# MD5133-A01-02.net
KiCad netlist of a schematic drawn in Altium Designer
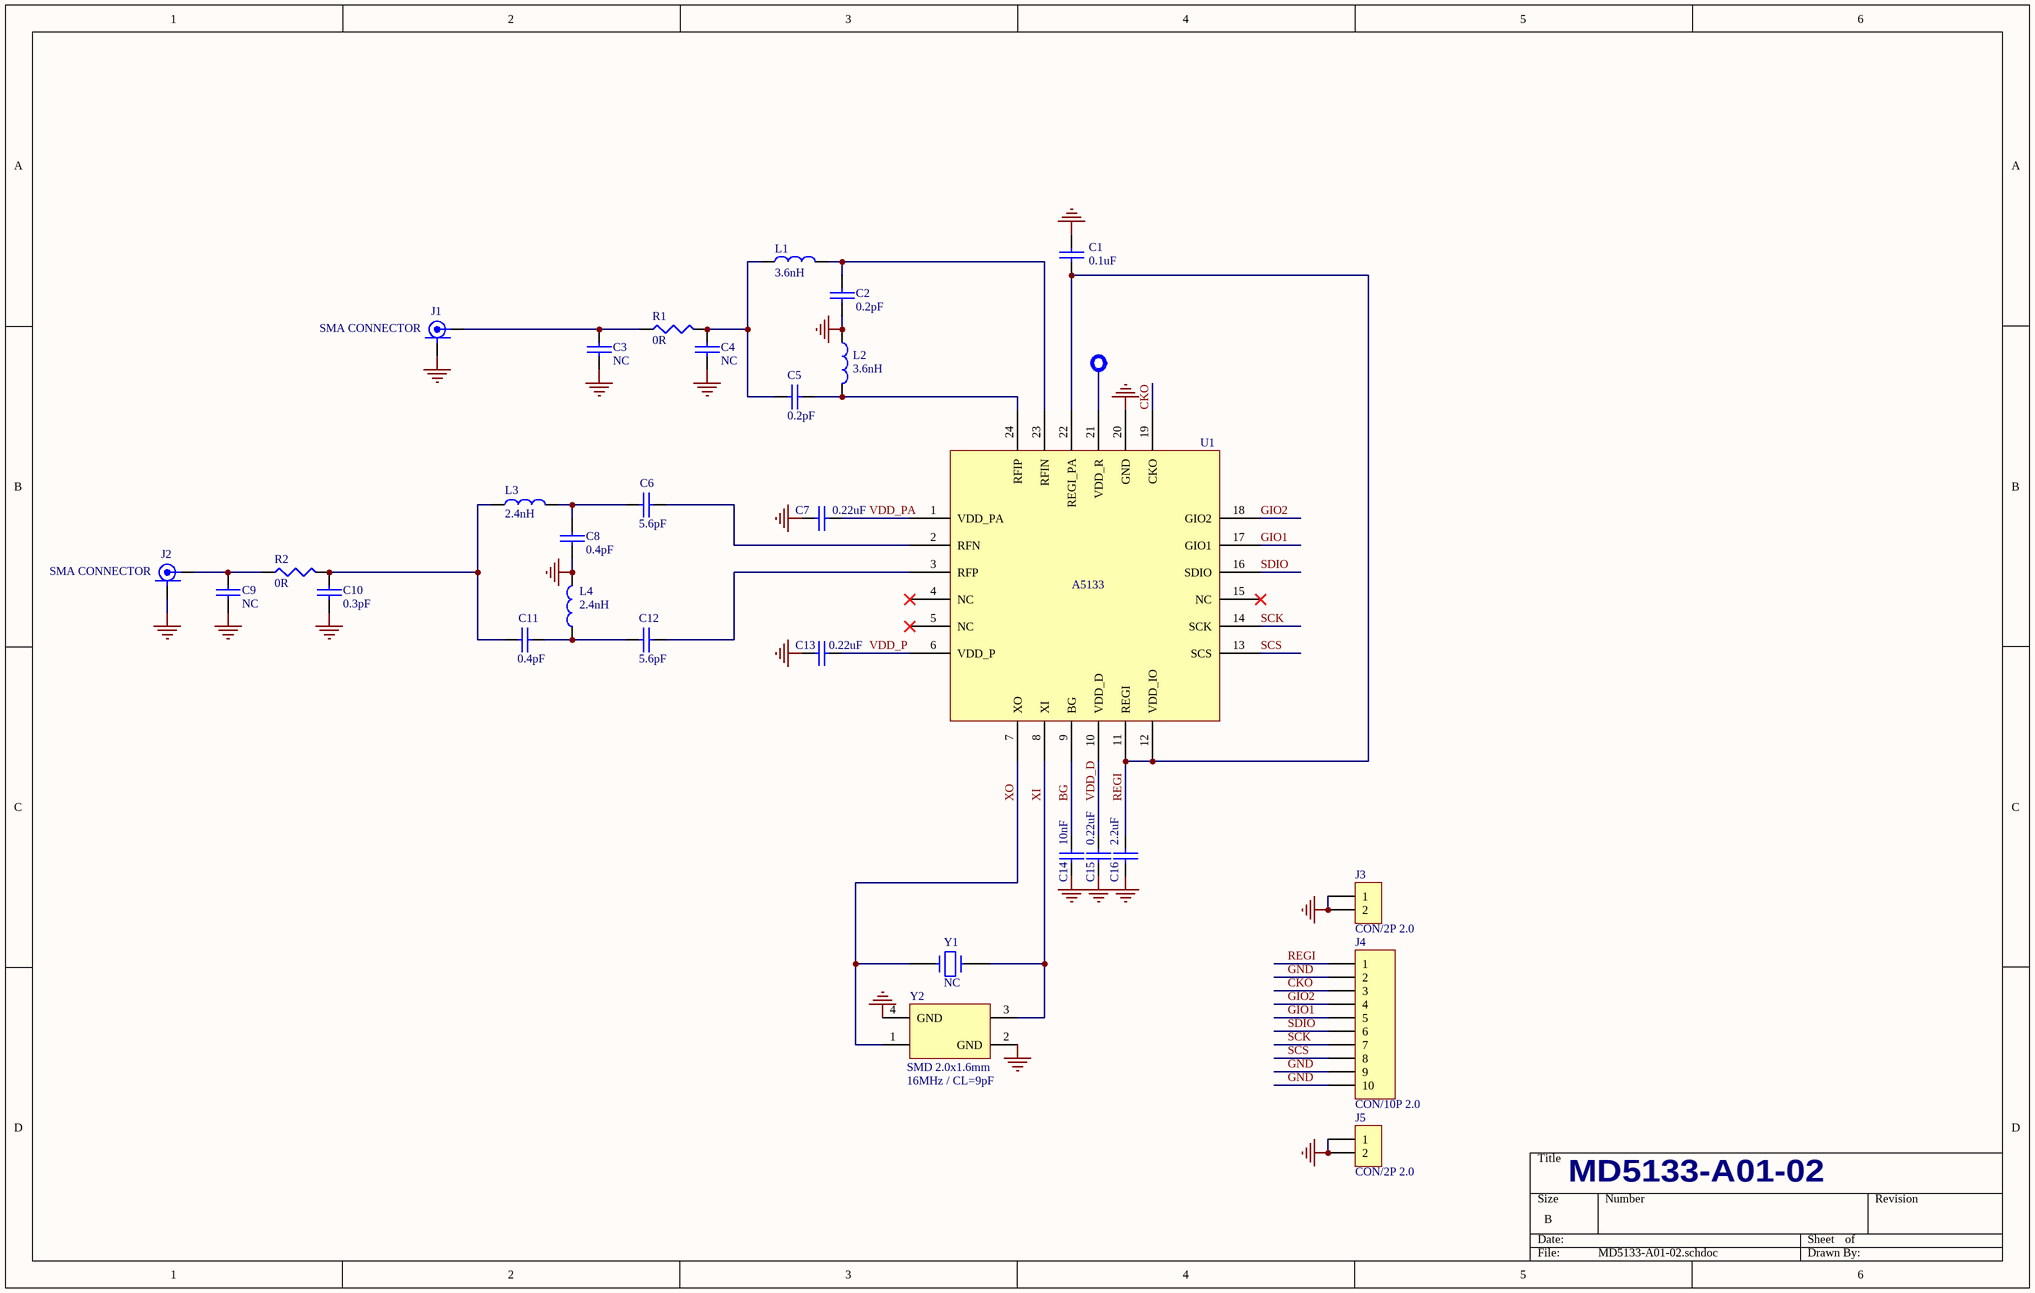
[diagram p0: MD5133-A01-02.schdoc]

(export (version "E")
  (design (tool "Eeschema 10.0.6"))
  (components
    (comp (ref "C1") (value "0.1uF") (footprint "0402") (libsource (lib "") (part "CAP_1")))
    (comp (ref "C2")
      (value "0.2pF")
      (footprint "0402")
      (description "Chip C")
      (libsource (lib "*") (part "C/0603"))
    )
    (comp (ref "C3")
      (value "NC")
      (footprint "0402")
      (description "Chip C")
      (libsource (lib "*") (part "C/0603"))
    )
    (comp (ref "C4")
      (value "NC")
      (footprint "0402")
      (description "Chip C")
      (libsource (lib "*") (part "C/0603"))
    )
    (comp (ref "C5")
      (value "0.2pF")
      (footprint "0402")
      (description "Chip C")
      (libsource (lib "*") (part "C/0603"))
    )
    (comp (ref "C6")
      (value "5.6pF")
      (footprint "0402")
      (description "Chip C")
      (libsource (lib "*") (part "C/0603"))
    )
    (comp (ref "C7") (value "0.22uF") (footprint "0402") (libsource (lib "") (part "CAP_1")))
    (comp (ref "C8")
      (value "0.4pF")
      (footprint "0402")
      (description "Chip C")
      (libsource (lib "*") (part "C/0603"))
    )
    (comp (ref "C9")
      (value "NC")
      (footprint "0402")
      (description "Chip C")
      (libsource (lib "*") (part "C/0603"))
    )
    (comp (ref "C10")
      (value "0.3pF")
      (footprint "0402")
      (description "Chip C")
      (libsource (lib "*") (part "C/0603"))
    )
    (comp (ref "C11")
      (value "0.4pF")
      (footprint "0402")
      (description "Chip C")
      (libsource (lib "*") (part "C/0603"))
    )
    (comp (ref "C12")
      (value "5.6pF")
      (footprint "0402")
      (description "Chip C")
      (libsource (lib "*") (part "C/0603"))
    )
    (comp (ref "C13") (value "0.22uF") (footprint "0402") (libsource (lib "") (part "CAP_1")))
    (comp (ref "C14") (value "10nF") (footprint "0402") (libsource (lib "*") (part "CAP")))
    (comp (ref "C15") (value "0.22uF") (footprint "0402") (libsource (lib "*") (part "CAP")))
    (comp (ref "C16") (value "2.2uF") (footprint "0402") (libsource (lib "*") (part "CAP")))
    (comp (ref "J1")
      (value "SMA CONNECTOR")
      (footprint "SMA CONNECTOR")
      (libsource (lib "AMICCOM-S") (part "SMA CONNECTOR"))
    )
    (comp (ref "J2")
      (value "SMA CONNECTOR")
      (footprint "SMA CONNECTOR")
      (libsource (lib "AMICCOM-S") (part "SMA CONNECTOR"))
    )
    (comp (ref "J3")
      (value "CON/2P 2.0")
      (footprint "HDR2_2.0")
      (description "Hole 36mil")
      (libsource (lib "*") (part "CON/2P 2.0"))
    )
    (comp (ref "J4")
      (value "CON/10P 2.0")
      (footprint "HDR10_2.0")
      (description "Hole 36mil")
      (libsource (lib "*") (part "CON/10P 2.0"))
    )
    (comp (ref "J5")
      (value "CON/2P 2.0")
      (footprint "HDR2_2.0")
      (description "Hole 36mil")
      (libsource (lib "*") (part "CON/2P 2.0"))
    )
    (comp (ref "L1") (value "3.6nH") (footprint "0402") (libsource (lib "") (part "L/0603_1")))
    (comp (ref "L2") (value "3.6nH") (footprint "0402") (libsource (lib "*") (part "L/0603")))
    (comp (ref "L3") (value "2.4nH") (footprint "0402") (libsource (lib "") (part "L/0603_2")))
    (comp (ref "L4") (value "2.4nH") (footprint "0402") (libsource (lib "*") (part "L/0603")))
    (comp (ref "R1")
      (value "0R")
      (footprint "0402")
      (description "Chip R")
      (libsource (lib "AMICCOM-S") (part "R/0402"))
    )
    (comp (ref "R2")
      (value "0R")
      (footprint "0402")
      (description "Chip R")
      (libsource (lib "AMICCOM-S") (part "R/0402"))
    )
    (comp (ref "U1")
      (value "A5133-U01")
      (footprint "QFN 4*4 24L_A7190")
      (libsource (lib "AMICCOM-S") (part "A5133_U01"))
    )
    (comp (ref "Y1")
      (value "NC")
      (footprint "XTAL1")
      (description "16MHz")
      (libsource (lib "*") (part "CRYSTAL"))
    )
    (comp (ref "Y2")
      (value "SMD 2.0x1.6mm")
      (footprint "XTAL_2.0 *1.6")
      (description "(TST)16MHz,Cl=9pF")
      (libsource (lib "*") (part "CRYSTAL/5*3.2"))
    )
  )
  (nets
    (net (code "1") (name "/BG") (class "Default")
      (node (ref "C14") (pin "1") (pinfunction "1_1") (pintype "passive"))
      (node (ref "U1") (pin "9") (pinfunction "BG_9") (pintype "passive"))
    )
    (net (code "2") (name "/CKO") (class "Default")
      (node (ref "J4") (pin "3") (pinfunction "3_3") (pintype "passive"))
      (node (ref "U1") (pin "19") (pinfunction "CKO_19") (pintype "passive"))
    )
    (net (code "3") (name "/GIO1") (class "Default")
      (node (ref "J4") (pin "5") (pinfunction "5_5") (pintype "passive"))
      (node (ref "U1") (pin "17") (pinfunction "GIO1_17") (pintype "passive"))
    )
    (net (code "4") (name "/GIO2") (class "Default")
      (node (ref "J4") (pin "4") (pinfunction "4_4") (pintype "passive"))
      (node (ref "U1") (pin "18") (pinfunction "GIO2_18") (pintype "passive"))
    )
    (net (code "5") (name "/REGI") (class "Default")
      (node (ref "C1") (pin "1") (pinfunction "1_1") (pintype "passive"))
      (node (ref "C16") (pin "1") (pinfunction "1_1") (pintype "passive"))
      (node (ref "J4") (pin "1") (pinfunction "1_1") (pintype "passive"))
      (node (ref "U1") (pin "11") (pinfunction "REGI_11") (pintype "passive"))
      (node (ref "U1") (pin "12") (pinfunction "VDD_IO_12") (pintype "passive"))
      (node (ref "U1") (pin "22") (pinfunction "REGI_PA_22") (pintype "passive"))
    )
    (net (code "6") (name "/SCK") (class "Default")
      (node (ref "J4") (pin "7") (pinfunction "7_7") (pintype "passive"))
      (node (ref "U1") (pin "14") (pinfunction "SCK_14") (pintype "passive"))
    )
    (net (code "7") (name "/SCS") (class "Default")
      (node (ref "J4") (pin "8") (pinfunction "8_8") (pintype "passive"))
      (node (ref "U1") (pin "13") (pinfunction "SCS_13") (pintype "passive"))
    )
    (net (code "8") (name "/SDIO") (class "Default")
      (node (ref "J4") (pin "6") (pinfunction "6_6") (pintype "passive"))
      (node (ref "U1") (pin "16") (pinfunction "SDIO_16") (pintype "passive"))
    )
    (net (code "9") (name "/VDD_D") (class "Default")
      (node (ref "C15") (pin "1") (pinfunction "1_1") (pintype "passive"))
      (node (ref "U1") (pin "10") (pinfunction "VDD_D_10") (pintype "passive"))
    )
    (net (code "10") (name "/VDD_P") (class "Default")
      (node (ref "C13") (pin "2") (pinfunction "2_2") (pintype "passive"))
      (node (ref "U1") (pin "6") (pinfunction "VDD_P_6") (pintype "passive"))
    )
    (net (code "11") (name "/VDD_PA") (class "Default")
      (node (ref "C7") (pin "2") (pinfunction "2_2") (pintype "passive"))
      (node (ref "U1") (pin "1") (pinfunction "VDD_PA_1") (pintype "passive"))
    )
    (net (code "12") (name "/XI") (class "Default")
      (node (ref "U1") (pin "8") (pinfunction "XI_8") (pintype "passive"))
      (node (ref "Y1") (pin "2") (pinfunction "2_2") (pintype "passive"))
      (node (ref "Y2") (pin "3") (pintype "passive"))
    )
    (net (code "13") (name "/XO") (class "Default")
      (node (ref "U1") (pin "7") (pinfunction "XO_7") (pintype "passive"))
      (node (ref "Y1") (pin "1") (pinfunction "1_1") (pintype "passive"))
      (node (ref "Y2") (pin "1") (pintype "passive"))
    )
    (net (code "14") (name "GND") (class "Default")
      (node (ref "C1") (pin "2") (pinfunction "2_2") (pintype "passive"))
      (node (ref "C10") (pin "2") (pinfunction "2_2") (pintype "passive"))
      (node (ref "C13") (pin "1") (pinfunction "1_1") (pintype "passive"))
      (node (ref "C14") (pin "2") (pinfunction "2_2") (pintype "passive"))
      (node (ref "C15") (pin "2") (pinfunction "2_2") (pintype "passive"))
      (node (ref "C16") (pin "2") (pinfunction "2_2") (pintype "passive"))
      (node (ref "C2") (pin "1") (pinfunction "1_1") (pintype "passive"))
      (node (ref "C3") (pin "1") (pinfunction "1_1") (pintype "passive"))
      (node (ref "C4") (pin "1") (pinfunction "1_1") (pintype "passive"))
      (node (ref "C7") (pin "1") (pinfunction "1_1") (pintype "passive"))
      (node (ref "C8") (pin "2") (pinfunction "2_2") (pintype "passive"))
      (node (ref "C9") (pin "2") (pinfunction "2_2") (pintype "passive"))
      (node (ref "J1") (pin "0") (pinfunction "SHIELD_0") (pintype "passive"))
      (node (ref "J2") (pin "0") (pinfunction "SHIELD_0") (pintype "passive"))
      (node (ref "J3") (pin "1") (pinfunction "1_1") (pintype "passive"))
      (node (ref "J3") (pin "2") (pinfunction "2_2") (pintype "passive"))
      (node (ref "J4") (pin "10") (pinfunction "10_10") (pintype "passive"))
      (node (ref "J4") (pin "2") (pinfunction "2_2") (pintype "passive"))
      (node (ref "J4") (pin "9") (pinfunction "9_9") (pintype "passive"))
      (node (ref "J5") (pin "1") (pinfunction "1_1") (pintype "passive"))
      (node (ref "J5") (pin "2") (pinfunction "2_2") (pintype "passive"))
      (node (ref "L2") (pin "1") (pinfunction "1_1") (pintype "passive"))
      (node (ref "L4") (pin "2") (pinfunction "2_2") (pintype "passive"))
      (node (ref "U1") (pin "20") (pinfunction "GND_20") (pintype "passive"))
      (node (ref "Y2") (pin "2") (pinfunction "GND_2") (pintype "passive"))
      (node (ref "Y2") (pin "4") (pinfunction "GND_4") (pintype "passive"))
    )
    (net (code "15") (name "Net-(C4-Pad2)") (class "Default")
      (node (ref "C4") (pin "2") (pinfunction "2_2") (pintype "passive"))
      (node (ref "C5") (pin "1") (pinfunction "1_1") (pintype "passive"))
      (node (ref "L1") (pin "1") (pinfunction "1_1") (pintype "passive"))
      (node (ref "R1") (pin "2") (pinfunction "2_2") (pintype "passive"))
    )
    (net (code "16") (name "Net-(C6-Pad1)") (class "Default")
      (node (ref "C6") (pin "1") (pinfunction "1_1") (pintype "passive"))
      (node (ref "C8") (pin "1") (pinfunction "1_1") (pintype "passive"))
      (node (ref "L3") (pin "1") (pinfunction "1_1") (pintype "passive"))
    )
    (net (code "17") (name "Net-(C10-Pad1)") (class "Default")
      (node (ref "C10") (pin "1") (pinfunction "1_1") (pintype "passive"))
      (node (ref "C11") (pin "2") (pinfunction "2_2") (pintype "passive"))
      (node (ref "L3") (pin "2") (pinfunction "2_2") (pintype "passive"))
      (node (ref "R2") (pin "2") (pinfunction "2_2") (pintype "passive"))
    )
    (net (code "18") (name "Net-(C11-Pad1)") (class "Default")
      (node (ref "C11") (pin "1") (pinfunction "1_1") (pintype "passive"))
      (node (ref "C12") (pin "1") (pinfunction "1_1") (pintype "passive"))
      (node (ref "L4") (pin "1") (pinfunction "1_1") (pintype "passive"))
    )
    (net (code "19") (name "Net-(J1-CENTER_1)") (class "Default")
      (node (ref "C3") (pin "2") (pinfunction "2_2") (pintype "passive"))
      (node (ref "J1") (pin "1") (pinfunction "CENTER_1_1") (pintype "passive"))
      (node (ref "R1") (pin "1") (pinfunction "1_1") (pintype "passive"))
    )
    (net (code "20") (name "Net-(J2-CENTER_1)") (class "Default")
      (node (ref "C9") (pin "1") (pinfunction "1_1") (pintype "passive"))
      (node (ref "J2") (pin "1") (pinfunction "CENTER_1_1") (pintype "passive"))
      (node (ref "R2") (pin "1") (pinfunction "1_1") (pintype "passive"))
    )
    (net (code "21") (name "Net-(U1-RFIN)") (class "Default")
      (node (ref "C2") (pin "2") (pinfunction "2_2") (pintype "passive"))
      (node (ref "L1") (pin "2") (pinfunction "2_2") (pintype "passive"))
      (node (ref "U1") (pin "23") (pinfunction "RFIN_23") (pintype "passive"))
    )
    (net (code "22") (name "Net-(U1-RFIP)") (class "Default")
      (node (ref "C5") (pin "2") (pinfunction "2_2") (pintype "passive"))
      (node (ref "L2") (pin "2") (pinfunction "2_2") (pintype "passive"))
      (node (ref "U1") (pin "24") (pinfunction "RFIP_24") (pintype "passive"))
    )
    (net (code "23") (name "Net-(U1-RFN)") (class "Default")
      (node (ref "C6") (pin "2") (pinfunction "2_2") (pintype "passive"))
      (node (ref "U1") (pin "2") (pinfunction "RFN_2") (pintype "passive"))
    )
    (net (code "24") (name "Net-(U1-RFP)") (class "Default")
      (node (ref "C12") (pin "2") (pinfunction "2_2") (pintype "passive"))
      (node (ref "U1") (pin "3") (pinfunction "RFP_3") (pintype "passive"))
    )
    (net (code "25") (name "unconnected-(U1-NC-Pad4)") (class "Default")
      (node (ref "U1") (pin "4") (pinfunction "NC_4") (pintype "passive+no_connect"))
    )
    (net (code "26") (name "unconnected-(U1-NC-Pad5)") (class "Default")
      (node (ref "U1") (pin "5") (pinfunction "NC_5") (pintype "passive+no_connect"))
    )
    (net (code "27") (name "unconnected-(U1-NC-Pad15)") (class "Default")
      (node (ref "U1") (pin "15") (pinfunction "NC_15") (pintype "passive+no_connect"))
    )
    (net (code "28") (name "unconnected-(U1-VDD_R-Pad21)") (class "Default")
      (node (ref "U1") (pin "21") (pinfunction "VDD_R_21") (pintype "passive"))
    )
  )
)
